# CDCF5801.net
KiCad netlist of a schematic drawn in Altium Designer
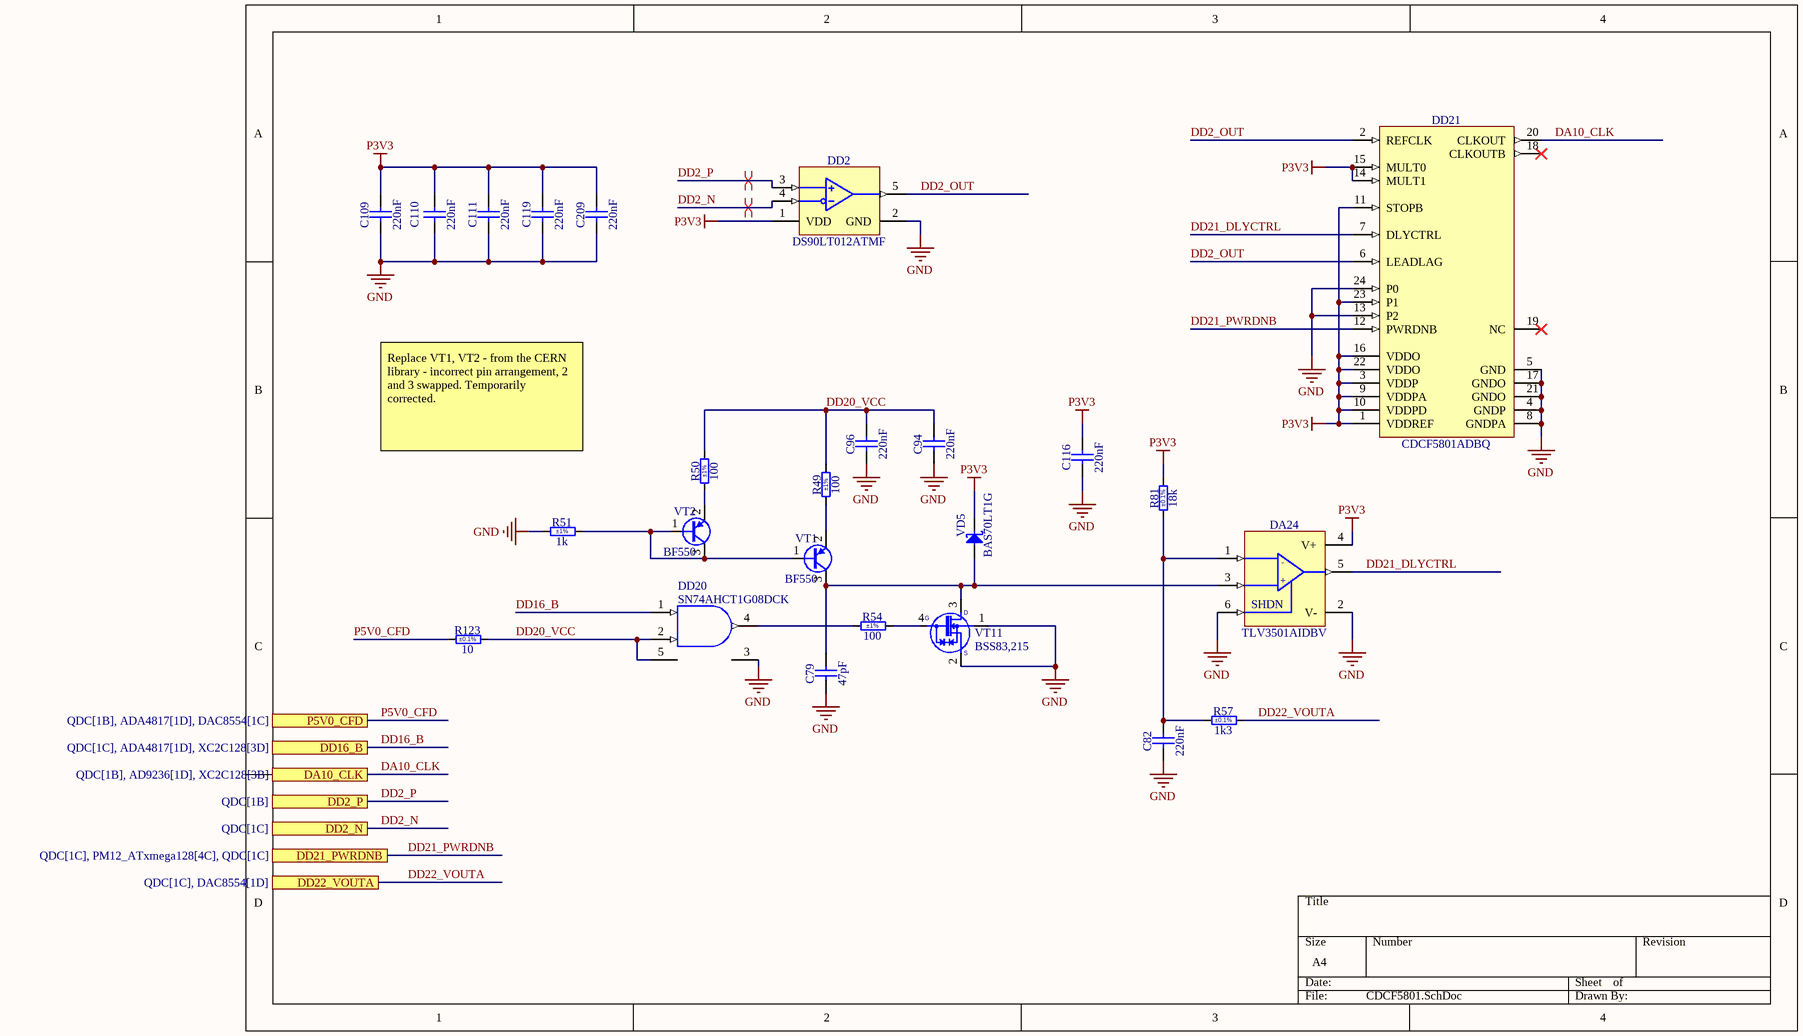
[diagram p0: CDCF5801.SchDoc]

(export (version "E")
  (design (tool "Eeschema 10.0.6"))
  (components
    (comp (ref "C79")
      (value "47pF")
      (footprint "CAPC2012X140N")
      (description "Non-polarised capacitor")
      (fields
        (field (name "PART NUMBER") "CC0805_47pF_50V_2%_X8R")
        (field (name "VOLTAGE") "50V")
        (field (name "AUTHOR") "CERN DEM HF")
      )
      (libsource (lib "Capacitors") (part "Capacitor - non polarized"))
    )
    (comp (ref "C82")
      (value "220nF")
      (footprint "CAPC2012X135N")
      (description "Non-polarised capacitor")
      (fields
        (field (name "PART NUMBER") "CC0805_220NF_50V_10%_X7R")
        (field (name "VOLTAGE") "50V")
        (field (name "AUTHOR") "CERN DEM JLC")
      )
      (libsource (lib "Capacitors") (part "Capacitor - non polarized"))
    )
    (comp (ref "C94")
      (value "220nF")
      (footprint "CAPC2012X135N")
      (description "Non-polarised capacitor")
      (fields
        (field (name "PART NUMBER") "CC0805_220NF_50V_10%_X7R")
        (field (name "VOLTAGE") "50V")
        (field (name "AUTHOR") "CERN DEM JLC")
      )
      (libsource (lib "Capacitors") (part "Capacitor - non polarized"))
    )
    (comp (ref "C96")
      (value "220nF")
      (footprint "CAPC2012X135N")
      (description "Non-polarised capacitor")
      (fields
        (field (name "PART NUMBER") "CC0805_220NF_50V_10%_X7R")
        (field (name "VOLTAGE") "50V")
        (field (name "AUTHOR") "CERN DEM JLC")
      )
      (libsource (lib "Capacitors") (part "Capacitor - non polarized"))
    )
    (comp (ref "C109")
      (value "220nF")
      (footprint "CAPC2012X135N")
      (description "Non-polarised capacitor")
      (fields
        (field (name "PART NUMBER") "CC0805_220NF_50V_10%_X7R")
        (field (name "VOLTAGE") "50V")
        (field (name "AUTHOR") "CERN DEM JLC")
      )
      (libsource (lib "Capacitors") (part "Capacitor - non polarized"))
    )
    (comp (ref "C110")
      (value "220nF")
      (footprint "CAPC2012X135N")
      (description "Non-polarised capacitor")
      (fields
        (field (name "PART NUMBER") "CC0805_220NF_50V_10%_X7R")
        (field (name "VOLTAGE") "50V")
        (field (name "AUTHOR") "CERN DEM JLC")
      )
      (libsource (lib "Capacitors") (part "Capacitor - non polarized"))
    )
    (comp (ref "C111")
      (value "220nF")
      (footprint "CAPC2012X135N")
      (description "Non-polarised capacitor")
      (fields
        (field (name "PART NUMBER") "CC0805_220NF_50V_10%_X7R")
        (field (name "VOLTAGE") "50V")
        (field (name "AUTHOR") "CERN DEM JLC")
      )
      (libsource (lib "Capacitors") (part "Capacitor - non polarized"))
    )
    (comp (ref "C116")
      (value "220nF")
      (footprint "CAPC2012X135N")
      (description "Non-polarised capacitor")
      (fields
        (field (name "PART NUMBER") "CC0805_220NF_50V_10%_X7R")
        (field (name "VOLTAGE") "50V")
        (field (name "AUTHOR") "CERN DEM JLC")
      )
      (libsource (lib "Capacitors") (part "Capacitor - non polarized"))
    )
    (comp (ref "C119")
      (value "220nF")
      (footprint "CAPC2012X135N")
      (description "Non-polarised capacitor")
      (fields
        (field (name "PART NUMBER") "CC0805_220NF_50V_10%_X7R")
        (field (name "VOLTAGE") "50V")
        (field (name "AUTHOR") "CERN DEM JLC")
      )
      (libsource (lib "Capacitors") (part "Capacitor - non polarized"))
    )
    (comp (ref "C209")
      (value "220nF")
      (footprint "CAPC2012X135N")
      (description "Non-polarised capacitor")
      (fields
        (field (name "PART NUMBER") "CC0805_220NF_50V_10%_X7R")
        (field (name "VOLTAGE") "50V")
        (field (name "AUTHOR") "CERN DEM JLC")
      )
      (libsource (lib "Capacitors") (part "Capacitor - non polarized"))
    )
    (comp (ref "DA24")
      (value "TLV3501AIDBV")
      (footprint "SOT95P280X145-6N")
      (description "Wideband, Fixed Gain, Video Buffer Amplifier With Disable")
      (fields (field (name "MANUFACTURER") "TEXAS INSTRUMENTS") (field (name "AUTHOR") "CERN DEM HF"))
      (libsource (lib "ICs And Semiconductors") (part "TLV3501AIDBV"))
    )
    (comp (ref "DD2")
      (value "DS90LT012ATMF")
      (footprint "SOT95P280X145-5N")
      (description "3V LVDS Single CMOS Differential Line Receiver")
      (fields (field (name "MANUFACTURER") "TEXAS INSTRUMENTS") (field (name "AUTHOR") "CERN DEM HF"))
      (libsource (lib "ICs And Semiconductors") (part "DS90LT012A"))
    )
    (comp (ref "DD20")
      (value "SN74AHCT1G08DCK")
      (footprint "SOT65P210X110-5N")
      (description "Single 2-Input AND Gate")
      (fields (field (name "MANUFACTURER") "TEXAS INSTRUMENTS") (field (name "AUTHOR") "CERN DEM HF"))
      (libsource (lib "ICs And Semiconductors") (part "741G08"))
    )
    (comp (ref "DD21")
      (value "CDCF5801ADBQ")
      (footprint "SOP63P600X175-24N")
      (description "Clock Multiplier with Delay Control and Phase Alignment")
      (fields (field (name "MANUFACTURER") "TEXAS INSTRUMENTS") (field (name "AUTHOR") "CERN DEM HF"))
      (libsource (lib "ICs And Semiconductors") (part "CDCF5801ADBQ"))
    )
    (comp (ref "R49")
      (value "100")
      (footprint "RESC2012X60N")
      (description "Resistor - 1%")
      (fields
        (field (name "TOLERANCE") "±1%")
        (field (name "PART NUMBER") "R0805_100R_1%_0.125W_100PPM")
        (field (name "POWER") "0.125W")
        (field (name "AUTHOR") "CERN DEM JLC")
      )
      (libsource (lib "Resistors") (part "Resistor - 1%"))
    )
    (comp (ref "R50")
      (value "100")
      (footprint "RESC2012X60N")
      (description "Resistor - 1%")
      (fields
        (field (name "TOLERANCE") "±1%")
        (field (name "PART NUMBER") "R0805_100R_1%_0.125W_100PPM")
        (field (name "POWER") "0.125W")
        (field (name "AUTHOR") "CERN DEM JLC")
      )
      (libsource (lib "Resistors") (part "Resistor - 1%"))
    )
    (comp (ref "R51")
      (value "1k")
      (footprint "RESC2012X60N")
      (description "Resistor - 1%")
      (fields
        (field (name "TOLERANCE") "±1%")
        (field (name "PART NUMBER") "R0805_1K_1%_0.125W_100PPM")
        (field (name "POWER") "0.125W")
        (field (name "AUTHOR") "CERN DEM JLC")
      )
      (libsource (lib "Resistors") (part "Resistor - 1%"))
    )
    (comp (ref "R54")
      (value "100")
      (footprint "RESC1608X55N")
      (description "Resistor - 1%")
      (fields
        (field (name "TOLERANCE") "±1%")
        (field (name "PART NUMBER") "R0603_100R_1%_0.1W_100PPM")
        (field (name "POWER") "0.1W")
        (field (name "AUTHOR") "CERN DEM JLC")
      )
      (libsource (lib "Resistors") (part "Resistor - 1%"))
    )
    (comp (ref "R57")
      (value "1k3")
      (footprint "RESC2012X60N")
      (description "Resistor - 0.1%")
      (fields
        (field (name "TOLERANCE") "±0.1%")
        (field (name "PART NUMBER") "R0805_1K3_0.1%_0.1W_10PPM")
        (field (name "POWER") "0.1W")
        (field (name "AUTHOR") "CERN DEM JLC")
      )
      (libsource (lib "Resistors") (part "Resistor - 0.1%"))
    )
    (comp (ref "R81")
      (value "18k")
      (footprint "RESC2012X60N")
      (description "Resistor - 0.1%")
      (fields
        (field (name "TOLERANCE") "±0.1%")
        (field (name "PART NUMBER") "R0805_18K_0.1%_0.125W_10PPM")
        (field (name "POWER") "0.125W")
        (field (name "AUTHOR") "CERN DEM HF")
      )
      (libsource (lib "Resistors") (part "Resistor - 0.1%"))
    )
    (comp (ref "R123")
      (value "10")
      (footprint "RESC2012X60N")
      (description "Resistor - 0.1%")
      (fields
        (field (name "TOLERANCE") "±0.1%")
        (field (name "PART NUMBER") "R0805_10R_0.1%_0.1W_10PPM")
        (field (name "POWER") "0.1W")
        (field (name "AUTHOR") "CERN DEM JLC")
      )
      (libsource (lib "Resistors") (part "Resistor - 0.1%"))
    )
    (comp (ref "VD5")
      (value "BAS70LT1G")
      (footprint "SOT95P240X110-3N")
      (description "Diode Schottky  Anode Pin 1 Cathode Pin 3 (Pas de pin 2)")
      (fields
        (field (name "VOLTAGE") "70V")
        (field (name "POWER") "70mA")
        (field (name "AUTHOR") "CERN DEM JLC")
      )
      (libsource (lib "ICs And Semiconductors") (part "Diode Schottky A1C3"))
    )
    (comp (ref "VT1")
      (value "BF550")
      (footprint "SOT95P230X110-3N")
      (description "PNP Transistor")
      (fields (field (name "MANUFACTURER") "NXP SEMICONDUCTORS") (field (name "AUTHOR") "CERN DEM HF"))
      (libsource (lib "ICs And Semiconductors") (part "PNP B1 C2 E3"))
    )
    (comp (ref "VT2")
      (value "BF550")
      (footprint "SOT95P230X110-3N")
      (description "PNP Transistor")
      (fields (field (name "MANUFACTURER") "NXP SEMICONDUCTORS") (field (name "AUTHOR") "CERN DEM HF"))
      (libsource (lib "ICs And Semiconductors") (part "PNP B1 C2 E3"))
    )
    (comp (ref "VT11")
      (value "BSS83,215")
      (footprint "SOT143N")
      (description "10V, 50 mA N-Channel Enhancement Switching Transistor")
      (fields (field (name "MANUFACTURER") "NXP SEMICONDUCTORS") (field (name "AUTHOR") "CERN DEM JLC"))
      (libsource (lib "ICs And Semiconductors") (part "BSS83"))
    )
  )
  (nets
    (net (code "1") (name "/DA10_CLK") (class "Default")
      (node (ref "DD21") (pin "20") (pinfunction "CLKOUT_20") (pintype "output"))
    )
    (net (code "2") (name "/DD2_N") (class "Default")
      (node (ref "DD2") (pin "4") (pinfunction "IN-_4") (pintype "input"))
    )
    (net (code "3") (name "/DD2_OUT") (class "Default")
      (node (ref "DD2") (pin "5") (pinfunction "TTLOUT_5") (pintype "output"))
      (node (ref "DD21") (pin "2") (pinfunction "REFCLK_2") (pintype "input"))
      (node (ref "DD21") (pin "6") (pinfunction "LEADLAG_6") (pintype "input"))
    )
    (net (code "4") (name "/DD2_P") (class "Default")
      (node (ref "DD2") (pin "3") (pinfunction "IN+_3") (pintype "input"))
    )
    (net (code "5") (name "/DD16_B") (class "Default")
      (node (ref "DD20") (pin "1") (pinfunction "B_1") (pintype "input"))
    )
    (net (code "6") (name "/DD20_VCC") (class "Default")
      (node (ref "C94") (pin "2") (pinfunction "2_2") (pintype "passive"))
      (node (ref "C96") (pin "2") (pinfunction "2_2") (pintype "passive"))
      (node (ref "DD20") (pin "2") (pinfunction "A_2") (pintype "input"))
      (node (ref "DD20") (pin "5") (pinfunction "VCC_5") (pintype "power_in"))
      (node (ref "R123") (pin "2") (pinfunction "2_2") (pintype "passive"))
      (node (ref "R49") (pin "2") (pinfunction "2_2") (pintype "passive"))
      (node (ref "R50") (pin "2") (pinfunction "2_2") (pintype "passive"))
    )
    (net (code "7") (name "/DD21_DLYCTRL") (class "Default")
      (node (ref "DA24") (pin "5") (pinfunction "OUT_5") (pintype "output"))
      (node (ref "DD21") (pin "7") (pinfunction "DLYCTRL_7") (pintype "input"))
    )
    (net (code "8") (name "/DD21_PWRDNB") (class "Default")
      (node (ref "DD21") (pin "12") (pinfunction "PWRDNB_12") (pintype "input"))
    )
    (net (code "9") (name "/DD22_VOUTA") (class "Default")
      (node (ref "R57") (pin "2") (pinfunction "2_2") (pintype "passive"))
    )
    (net (code "10") (name "/P5V0_CFD") (class "Default")
      (node (ref "R123") (pin "1") (pinfunction "1_1") (pintype "passive"))
    )
    (net (code "11") (name "GND") (class "Default")
      (node (ref "C109") (pin "1") (pinfunction "1_1") (pintype "passive"))
      (node (ref "C110") (pin "1") (pinfunction "1_1") (pintype "passive"))
      (node (ref "C111") (pin "1") (pinfunction "1_1") (pintype "passive"))
      (node (ref "C116") (pin "1") (pinfunction "1_1") (pintype "passive"))
      (node (ref "C119") (pin "1") (pinfunction "1_1") (pintype "passive"))
      (node (ref "C209") (pin "1") (pinfunction "1_1") (pintype "passive"))
      (node (ref "C79") (pin "1") (pinfunction "1_1") (pintype "passive"))
      (node (ref "C82") (pin "1") (pinfunction "1_1") (pintype "passive"))
      (node (ref "C94") (pin "1") (pinfunction "1_1") (pintype "passive"))
      (node (ref "C96") (pin "1") (pinfunction "1_1") (pintype "passive"))
      (node (ref "DA24") (pin "2") (pinfunction "V-_2") (pintype "power_in"))
      (node (ref "DA24") (pin "6") (pinfunction "SHDN_6") (pintype "input"))
      (node (ref "DD2") (pin "2") (pinfunction "GND_2") (pintype "power_in"))
      (node (ref "DD20") (pin "3") (pinfunction "GND_3") (pintype "power_in"))
      (node (ref "DD21") (pin "13") (pinfunction "P2_13") (pintype "input"))
      (node (ref "DD21") (pin "17") (pinfunction "GNDO_17") (pintype "power_in"))
      (node (ref "DD21") (pin "21") (pinfunction "GNDO_21") (pintype "power_in"))
      (node (ref "DD21") (pin "24") (pinfunction "P0_24") (pintype "input"))
      (node (ref "DD21") (pin "4") (pinfunction "GNDP_4") (pintype "power_in"))
      (node (ref "DD21") (pin "5") (pinfunction "GND_5") (pintype "power_in"))
      (node (ref "DD21") (pin "8") (pinfunction "GNDPA_8") (pintype "power_in"))
      (node (ref "R51") (pin "1") (pinfunction "1_1") (pintype "passive"))
      (node (ref "VT11") (pin "1") (pinfunction "SUB_1") (pintype "passive"))
      (node (ref "VT11") (pin "2") (pinfunction "S_2") (pintype "passive"))
    )
    (net (code "12") (name "Net-(DA24-+IN)") (class "Default")
      (node (ref "C79") (pin "2") (pinfunction "2_2") (pintype "passive"))
      (node (ref "DA24") (pin "3") (pinfunction "+IN_3") (pintype "input"))
      (node (ref "VD5") (pin "1") (pinfunction "A_1") (pintype "passive"))
      (node (ref "VT1") (pin "3") (pinfunction "E_3") (pintype "passive"))
      (node (ref "VT11") (pin "3") (pinfunction "D_3") (pintype "passive"))
    )
    (net (code "13") (name "Net-(DA24--IN)") (class "Default")
      (node (ref "C82") (pin "2") (pinfunction "2_2") (pintype "passive"))
      (node (ref "DA24") (pin "1") (pinfunction "-IN_1") (pintype "input"))
      (node (ref "R57") (pin "1") (pinfunction "1_1") (pintype "passive"))
      (node (ref "R81") (pin "1") (pinfunction "1_1") (pintype "passive"))
    )
    (net (code "14") (name "Net-(DD20-Y)") (class "Default")
      (node (ref "DD20") (pin "4") (pinfunction "Y_4") (pintype "output"))
      (node (ref "R54") (pin "1") (pinfunction "1_1") (pintype "passive"))
    )
    (net (code "15") (name "Net-(VT1-B)") (class "Default")
      (node (ref "R51") (pin "2") (pinfunction "2_2") (pintype "passive"))
      (node (ref "VT1") (pin "1") (pinfunction "B_1") (pintype "passive"))
      (node (ref "VT2") (pin "1") (pinfunction "B_1") (pintype "passive"))
      (node (ref "VT2") (pin "3") (pinfunction "E_3") (pintype "passive"))
    )
    (net (code "16") (name "Net-(VT1-C)") (class "Default")
      (node (ref "R49") (pin "1") (pinfunction "1_1") (pintype "passive"))
      (node (ref "VT1") (pin "2") (pinfunction "C_2") (pintype "passive"))
    )
    (net (code "17") (name "Net-(VT2-C)") (class "Default")
      (node (ref "R50") (pin "1") (pinfunction "1_1") (pintype "passive"))
      (node (ref "VT2") (pin "2") (pinfunction "C_2") (pintype "passive"))
    )
    (net (code "18") (name "Net-(VT11-G)") (class "Default")
      (node (ref "R54") (pin "2") (pinfunction "2_2") (pintype "passive"))
      (node (ref "VT11") (pin "4") (pinfunction "G_4") (pintype "passive"))
    )
    (net (code "19") (name "P3V3") (class "Default")
      (node (ref "C109") (pin "2") (pinfunction "2_2") (pintype "passive"))
      (node (ref "C110") (pin "2") (pinfunction "2_2") (pintype "passive"))
      (node (ref "C111") (pin "2") (pinfunction "2_2") (pintype "passive"))
      (node (ref "C116") (pin "2") (pinfunction "2_2") (pintype "passive"))
      (node (ref "C119") (pin "2") (pinfunction "2_2") (pintype "passive"))
      (node (ref "C209") (pin "2") (pinfunction "2_2") (pintype "passive"))
      (node (ref "DA24") (pin "4") (pinfunction "V+_4") (pintype "power_in"))
      (node (ref "DD2") (pin "1") (pinfunction "VDD_1") (pintype "power_in"))
      (node (ref "DD21") (pin "1") (pinfunction "VDDREF_1") (pintype "power_in"))
      (node (ref "DD21") (pin "10") (pinfunction "VDDPD_10") (pintype "power_in"))
      (node (ref "DD21") (pin "11") (pinfunction "STOPB_11") (pintype "input"))
      (node (ref "DD21") (pin "14") (pinfunction "MULT1_14") (pintype "input"))
      (node (ref "DD21") (pin "15") (pinfunction "MULT0_15") (pintype "input"))
      (node (ref "DD21") (pin "16") (pinfunction "VDDO_16") (pintype "power_in"))
      (node (ref "DD21") (pin "22") (pinfunction "VDDO_22") (pintype "power_in"))
      (node (ref "DD21") (pin "23") (pinfunction "P1_23") (pintype "input"))
      (node (ref "DD21") (pin "3") (pinfunction "VDDP_3") (pintype "power_in"))
      (node (ref "DD21") (pin "9") (pinfunction "VDDPA_9") (pintype "power_in"))
      (node (ref "R81") (pin "2") (pinfunction "2_2") (pintype "passive"))
      (node (ref "VD5") (pin "3") (pinfunction "C_3") (pintype "passive"))
    )
    (net (code "20") (name "unconnected-(DD21-CLKOUTB-Pad18)") (class "Default")
      (node (ref "DD21") (pin "18") (pinfunction "CLKOUTB_18") (pintype "output+no_connect"))
    )
    (net (code "21") (name "unconnected-(DD21-NC-Pad19)") (class "Default")
      (node (ref "DD21") (pin "19") (pinfunction "NC_19") (pintype "passive+no_connect"))
    )
  )
)
